# Fireplace_Control.net
KiCad netlist of a schematic drawn in EAGLE
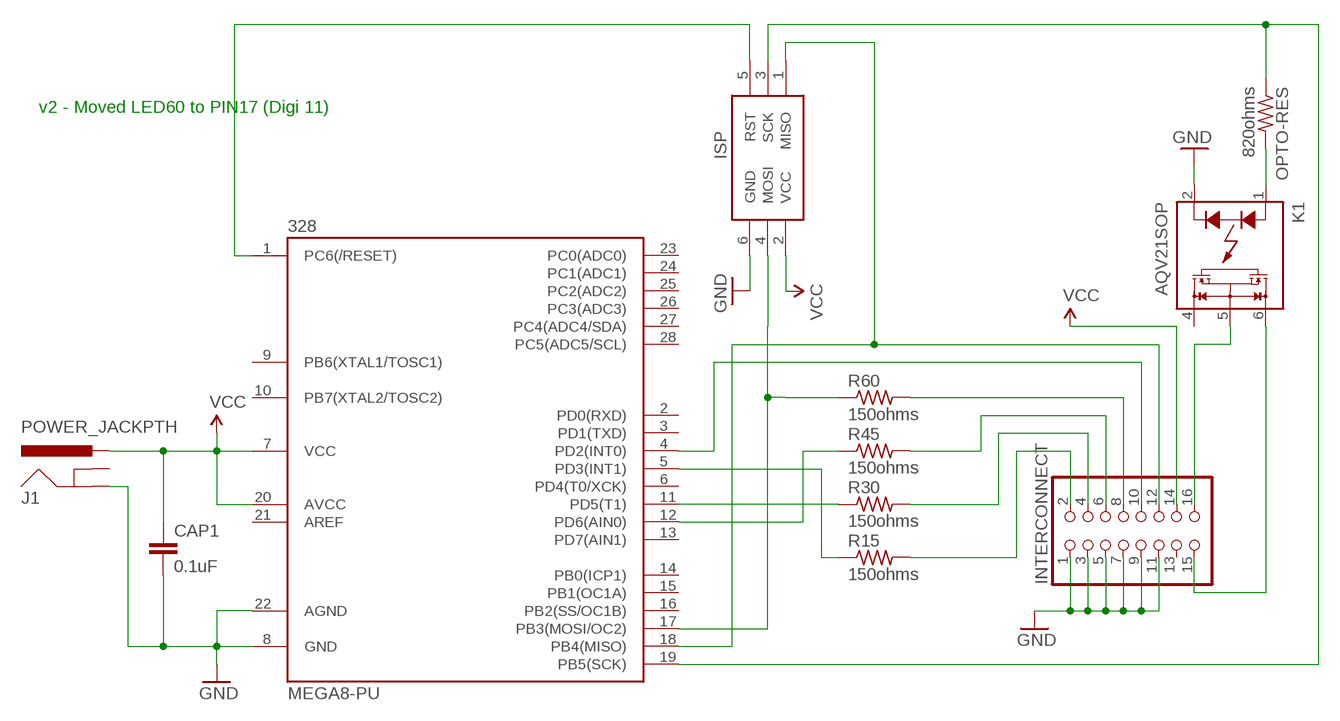
[diagram p0: schematic, sheet 1]

(export (version "E")
  (design (tool "Eeschema 10.0.6"))
  (components
    (comp (ref "328")
      (value "MEGA8-PU")
      (footprint "eagle-import:DIL28-3")
      (libsource (lib "eagle-import") (part "MEGA8-PU"))
    )
    (comp (ref "CAP1")
      (value "0.1uF")
      (footprint "eagle-import:CAP-PTH-SMALL-KIT")
      (libsource (lib "eagle-import") (part "CAPKIT"))
    )
    (comp (ref "INTERCONNECT")
      (value "PINHD-2X8")
      (footprint "eagle-import:2X08")
      (libsource (lib "eagle-import") (part "PINHD-2X8"))
    )
    (comp (ref "ISP")
      (value "AVRISP-6")
      (footprint "eagle-import:AVRISP")
      (libsource (lib "eagle-import") (part "AVRISP-6"))
    )
    (comp (ref "J1")
      (value "POWER_JACKPTH")
      (footprint "eagle-import:POWER_JACK_PTH")
      (libsource (lib "eagle-import") (part "POWER_JACKPTH"))
    )
    (comp (ref "K1")
      (value "AQV21SOP")
      (footprint "eagle-import:SOP06")
      (libsource (lib "eagle-import") (part "AQVSOP21"))
    )
    (comp (ref "OPTO-RES")
      (value "820ohms")
      (footprint "eagle-import:0207_2V")
      (libsource (lib "eagle-import") (part "R-US_0207/2V"))
    )
    (comp (ref "R15")
      (value "150ohms")
      (footprint "eagle-import:0207_2V")
      (libsource (lib "eagle-import") (part "R-US_0207/2V"))
    )
    (comp (ref "R30")
      (value "150ohms")
      (footprint "eagle-import:0207_2V")
      (libsource (lib "eagle-import") (part "R-US_0207/2V"))
    )
    (comp (ref "R45")
      (value "150ohms")
      (footprint "eagle-import:0207_2V")
      (libsource (lib "eagle-import") (part "R-US_0207/2V"))
    )
    (comp (ref "R60")
      (value "150ohms")
      (footprint "eagle-import:0207_2V")
      (libsource (lib "eagle-import") (part "R-US_0207/2V"))
    )
  )
  (nets
    (net (code "1") (name "GND") (class "Default")
      (node (ref "328") (pin "22") (pinfunction "AGND_22") (pintype "power_in"))
      (node (ref "328") (pin "8") (pinfunction "GND_8") (pintype "power_in"))
      (node (ref "CAP1") (pin "2") (pinfunction "2_2") (pintype "passive"))
      (node (ref "INTERCONNECT") (pin "1") (pinfunction "1_1") (pintype "passive"))
      (node (ref "INTERCONNECT") (pin "11") (pinfunction "11_11") (pintype "passive"))
      (node (ref "INTERCONNECT") (pin "3") (pinfunction "3_3") (pintype "passive"))
      (node (ref "INTERCONNECT") (pin "5") (pinfunction "5_5") (pintype "passive"))
      (node (ref "INTERCONNECT") (pin "7") (pinfunction "7_7") (pintype "passive"))
      (node (ref "INTERCONNECT") (pin "9") (pinfunction "9_9") (pintype "passive"))
      (node (ref "ISP") (pin "6") (pinfunction "GND_6") (pintype "power_in"))
      (node (ref "J1") (pin "GND") (pinfunction "GND_GND") (pintype "bidirectional"))
      (node (ref "K1") (pin "2") (pinfunction "K_2") (pintype "passive"))
    )
    (net (code "2") (name "Net-(328-PB3(MOSI{slash}OC2))") (class "Default")
      (node (ref "328") (pin "17") (pinfunction "PB3(MOSI/OC2)_17") (pintype "bidirectional"))
      (node (ref "ISP") (pin "4") (pinfunction "MOSI_4") (pintype "output"))
      (node (ref "R60") (pin "1") (pinfunction "1_1") (pintype "passive"))
    )
    (net (code "3") (name "Net-(328-PB4(MISO))") (class "Default")
      (node (ref "328") (pin "18") (pinfunction "PB4(MISO)_18") (pintype "bidirectional"))
      (node (ref "INTERCONNECT") (pin "12") (pinfunction "12_12") (pintype "passive"))
      (node (ref "ISP") (pin "1") (pinfunction "MISO_1") (pintype "input"))
    )
    (net (code "4") (name "Net-(328-PB5(SCK))") (class "Default")
      (node (ref "328") (pin "19") (pinfunction "PB5(SCK)_19") (pintype "bidirectional"))
      (node (ref "ISP") (pin "3") (pinfunction "SCK_3") (pintype "output"))
      (node (ref "OPTO-RES") (pin "1") (pinfunction "1_1") (pintype "passive"))
    )
    (net (code "5") (name "Net-(328-PC6({slash}RESET))") (class "Default")
      (node (ref "328") (pin "1") (pinfunction "PC6(/RESET)_1") (pintype "bidirectional"))
      (node (ref "ISP") (pin "5") (pinfunction "RST_5") (pintype "output"))
    )
    (net (code "6") (name "Net-(328-PD2(INT0))") (class "Default")
      (node (ref "328") (pin "4") (pinfunction "PD2(INT0)_4") (pintype "bidirectional"))
      (node (ref "INTERCONNECT") (pin "10") (pinfunction "10_10") (pintype "passive"))
    )
    (net (code "7") (name "Net-(328-PD3(INT1))") (class "Default")
      (node (ref "328") (pin "5") (pinfunction "PD3(INT1)_5") (pintype "bidirectional"))
      (node (ref "R15") (pin "1") (pinfunction "1_1") (pintype "passive"))
    )
    (net (code "8") (name "Net-(328-PD5(T1))") (class "Default")
      (node (ref "328") (pin "11") (pinfunction "PD5(T1)_11") (pintype "bidirectional"))
      (node (ref "R30") (pin "1") (pinfunction "1_1") (pintype "passive"))
    )
    (net (code "9") (name "Net-(328-PD6(AIN0))") (class "Default")
      (node (ref "328") (pin "12") (pinfunction "PD6(AIN0)_12") (pintype "bidirectional"))
      (node (ref "R45") (pin "1") (pinfunction "1_1") (pintype "passive"))
    )
    (net (code "10") (name "Net-(INTERCONNECT-Pad2)") (class "Default")
      (node (ref "INTERCONNECT") (pin "2") (pinfunction "2_2") (pintype "passive"))
      (node (ref "R15") (pin "2") (pinfunction "2_2") (pintype "passive"))
    )
    (net (code "11") (name "Net-(INTERCONNECT-Pad4)") (class "Default")
      (node (ref "INTERCONNECT") (pin "4") (pinfunction "4_4") (pintype "passive"))
      (node (ref "R30") (pin "2") (pinfunction "2_2") (pintype "passive"))
    )
    (net (code "12") (name "Net-(INTERCONNECT-Pad6)") (class "Default")
      (node (ref "INTERCONNECT") (pin "6") (pinfunction "6_6") (pintype "passive"))
      (node (ref "R45") (pin "2") (pinfunction "2_2") (pintype "passive"))
    )
    (net (code "13") (name "Net-(INTERCONNECT-Pad8)") (class "Default")
      (node (ref "INTERCONNECT") (pin "8") (pinfunction "8_8") (pintype "passive"))
      (node (ref "R60") (pin "2") (pinfunction "2_2") (pintype "passive"))
    )
    (net (code "14") (name "Net-(K1-A)") (class "Default")
      (node (ref "K1") (pin "1") (pinfunction "A_1") (pintype "passive"))
      (node (ref "OPTO-RES") (pin "2") (pinfunction "2_2") (pintype "passive"))
    )
    (net (code "15") (name "Net-(K1-D1)") (class "Default")
      (node (ref "INTERCONNECT") (pin "15") (pinfunction "15_15") (pintype "passive"))
      (node (ref "K1") (pin "6") (pinfunction "D1_6") (pintype "passive"))
    )
    (net (code "16") (name "Net-(K1-S)") (class "Default")
      (node (ref "INTERCONNECT") (pin "16") (pinfunction "16_16") (pintype "passive"))
      (node (ref "K1") (pin "5") (pinfunction "S_5") (pintype "passive"))
    )
    (net (code "17") (name "VCC") (class "Default")
      (node (ref "328") (pin "20") (pinfunction "AVCC_20") (pintype "passive"))
      (node (ref "328") (pin "7") (pinfunction "VCC_7") (pintype "power_in"))
      (node (ref "CAP1") (pin "1") (pinfunction "1_1") (pintype "passive"))
      (node (ref "INTERCONNECT") (pin "14") (pinfunction "14_14") (pintype "passive"))
      (node (ref "ISP") (pin "2") (pinfunction "VCC_2") (pintype "power_in"))
      (node (ref "J1") (pin "PWR") (pinfunction "PWR_PWR") (pintype "bidirectional"))
    )
    (net (code "18") (name "unconnected-(328-AREF-Pad21)") (class "Default")
      (node (ref "328") (pin "21") (pinfunction "AREF_21") (pintype "passive"))
    )
    (net (code "19") (name "unconnected-(328-PB0(ICP1)-Pad14)") (class "Default")
      (node (ref "328") (pin "14") (pinfunction "PB0(ICP1)_14") (pintype "bidirectional"))
    )
    (net (code "20") (name "unconnected-(328-PB1(OC1A)-Pad15)") (class "Default")
      (node (ref "328") (pin "15") (pinfunction "PB1(OC1A)_15") (pintype "bidirectional"))
    )
    (net (code "21") (name "unconnected-(328-PB2(SS{slash}OC1B)-Pad16)") (class "Default")
      (node (ref "328") (pin "16") (pinfunction "PB2(SS/OC1B)_16") (pintype "bidirectional"))
    )
    (net (code "22") (name "unconnected-(328-PB6(XTAL1{slash}TOSC1)-Pad9)") (class "Default")
      (node (ref "328") (pin "9") (pinfunction "PB6(XTAL1/TOSC1)_9") (pintype "bidirectional"))
    )
    (net (code "23") (name "unconnected-(328-PB7(XTAL2{slash}TOSC2)-Pad10)") (class "Default")
      (node (ref "328") (pin "10") (pinfunction "PB7(XTAL2/TOSC2)_10") (pintype "bidirectional"))
    )
    (net (code "24") (name "unconnected-(328-PC0(ADC0)-Pad23)") (class "Default")
      (node (ref "328") (pin "23") (pinfunction "PC0(ADC0)_23") (pintype "bidirectional"))
    )
    (net (code "25") (name "unconnected-(328-PC1(ADC1)-Pad24)") (class "Default")
      (node (ref "328") (pin "24") (pinfunction "PC1(ADC1)_24") (pintype "bidirectional"))
    )
    (net (code "26") (name "unconnected-(328-PC2(ADC2)-Pad25)") (class "Default")
      (node (ref "328") (pin "25") (pinfunction "PC2(ADC2)_25") (pintype "bidirectional"))
    )
    (net (code "27") (name "unconnected-(328-PC3(ADC3)-Pad26)") (class "Default")
      (node (ref "328") (pin "26") (pinfunction "PC3(ADC3)_26") (pintype "bidirectional"))
    )
    (net (code "28") (name "unconnected-(328-PC4(ADC4{slash}SDA)-Pad27)") (class "Default")
      (node (ref "328") (pin "27") (pinfunction "PC4(ADC4/SDA)_27") (pintype "bidirectional"))
    )
    (net (code "29") (name "unconnected-(328-PC5(ADC5{slash}SCL)-Pad28)") (class "Default")
      (node (ref "328") (pin "28") (pinfunction "PC5(ADC5/SCL)_28") (pintype "bidirectional"))
    )
    (net (code "30") (name "unconnected-(328-PD0(RXD)-Pad2)") (class "Default")
      (node (ref "328") (pin "2") (pinfunction "PD0(RXD)_2") (pintype "bidirectional"))
    )
    (net (code "31") (name "unconnected-(328-PD1(TXD)-Pad3)") (class "Default")
      (node (ref "328") (pin "3") (pinfunction "PD1(TXD)_3") (pintype "bidirectional"))
    )
    (net (code "32") (name "unconnected-(328-PD4(T0{slash}XCK)-Pad6)") (class "Default")
      (node (ref "328") (pin "6") (pinfunction "PD4(T0/XCK)_6") (pintype "bidirectional"))
    )
    (net (code "33") (name "unconnected-(328-PD7(AIN1)-Pad13)") (class "Default")
      (node (ref "328") (pin "13") (pinfunction "PD7(AIN1)_13") (pintype "bidirectional"))
    )
    (net (code "34") (name "unconnected-(INTERCONNECT-Pad13)") (class "Default")
      (node (ref "INTERCONNECT") (pin "13") (pinfunction "13_13") (pintype "passive"))
    )
    (net (code "35") (name "unconnected-(J1-PadGNDBREAK)") (class "Default")
      (node (ref "J1") (pin "GNDBREAK") (pinfunction "GNDBREAK_GNDBREAK") (pintype "bidirectional"))
    )
    (net (code "36") (name "unconnected-(K1-D2-Pad4)") (class "Default")
      (node (ref "K1") (pin "4") (pinfunction "D2_4") (pintype "passive"))
    )
  )
)
